# 07_Mechanical.net
KiCad netlist of a schematic drawn in Altium Designer
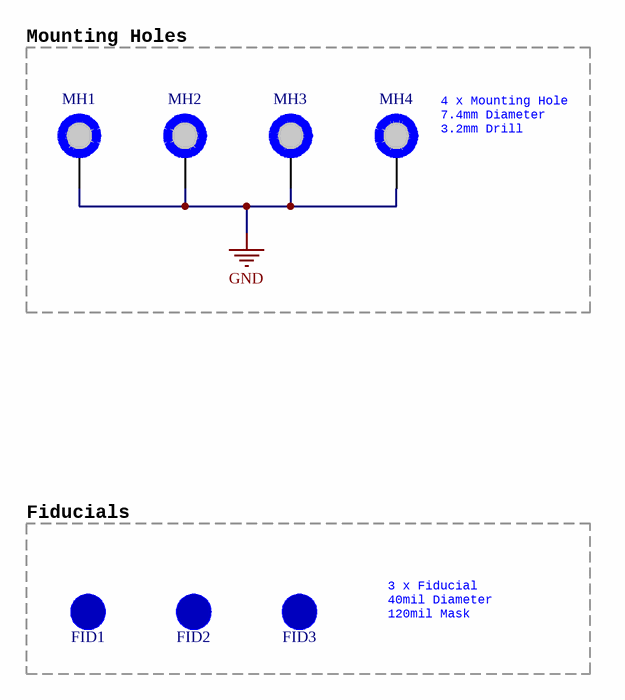
[diagram p0: 07.Mechanical.SchDoc]

(export (version "E")
  (design (tool "Eeschema 10.0.6"))
  (components
    (comp (ref "FID1")
      (value "FID_1MMC")
      (footprint "FID_40X120D")
      (description "Fiducial 40mil Diameter, 120mil Mask")
      (libsource (lib "iMX6 Rex Development Baseboard V1I1") (part "FID_1MMC"))
    )
    (comp (ref "FID2")
      (value "FID_1MMC")
      (footprint "FID_40X120D")
      (description "Fiducial 40mil Diameter, 120mil Mask")
      (libsource (lib "iMX6 Rex Development Baseboard V1I1") (part "FID_1MMC"))
    )
    (comp (ref "FID3")
      (value "FID_1MMC")
      (footprint "FID_40X120D")
      (description "Fiducial 40mil Diameter, 120mil Mask")
      (libsource (lib "iMX6 Rex Development Baseboard V1I1") (part "FID_1MMC"))
    )
    (comp (ref "MH1")
      (value "MH_7.4MMC_3.2MMD")
      (footprint "MH_7.4MMD_3.2MMD_VIA_SUPPORT")
      (description "Mounting Hole 7.4mm Diameter, 3.2mm Drill")
      (libsource (lib "Smart_Wifi_Control_System_Rev_A.1.0") (part "MH_7.4MMC_3.2MMD"))
    )
    (comp (ref "MH2")
      (value "MH_7.4MMC_3.2MMD")
      (footprint "MH_7.4MMD_3.2MMD_VIA_SUPPORT")
      (description "Mounting Hole 7.4mm Diameter, 3.2mm Drill")
      (libsource (lib "Smart_Wifi_Control_System_Rev_A.1.0") (part "MH_7.4MMC_3.2MMD"))
    )
    (comp (ref "MH3")
      (value "MH_7.4MMC_3.2MMD")
      (footprint "MH_7.4MMD_3.2MMD_VIA_SUPPORT")
      (description "Mounting Hole 7.4mm Diameter, 3.2mm Drill")
      (libsource (lib "Smart_Wifi_Control_System_Rev_A.1.0") (part "MH_7.4MMC_3.2MMD"))
    )
    (comp (ref "MH4")
      (value "MH_7.4MMC_3.2MMD")
      (footprint "MH_7.4MMD_3.2MMD_VIA_SUPPORT")
      (description "Mounting Hole 7.4mm Diameter, 3.2mm Drill")
      (libsource (lib "Smart_Wifi_Control_System_Rev_A.1.0") (part "MH_7.4MMC_3.2MMD"))
    )
  )
  (nets
    (net (code "1") (name "GND") (class "Default")
      (node (ref "MH1") (pin "1") (pinfunction "1_1") (pintype "passive"))
      (node (ref "MH2") (pin "1") (pinfunction "1_1") (pintype "passive"))
      (node (ref "MH3") (pin "1") (pinfunction "1_1") (pintype "passive"))
      (node (ref "MH4") (pin "1") (pinfunction "1_1") (pintype "passive"))
    )
  )
)
